# EctoControlAdapter.net
KiCad netlist of a schematic drawn in EasyEDA Pro
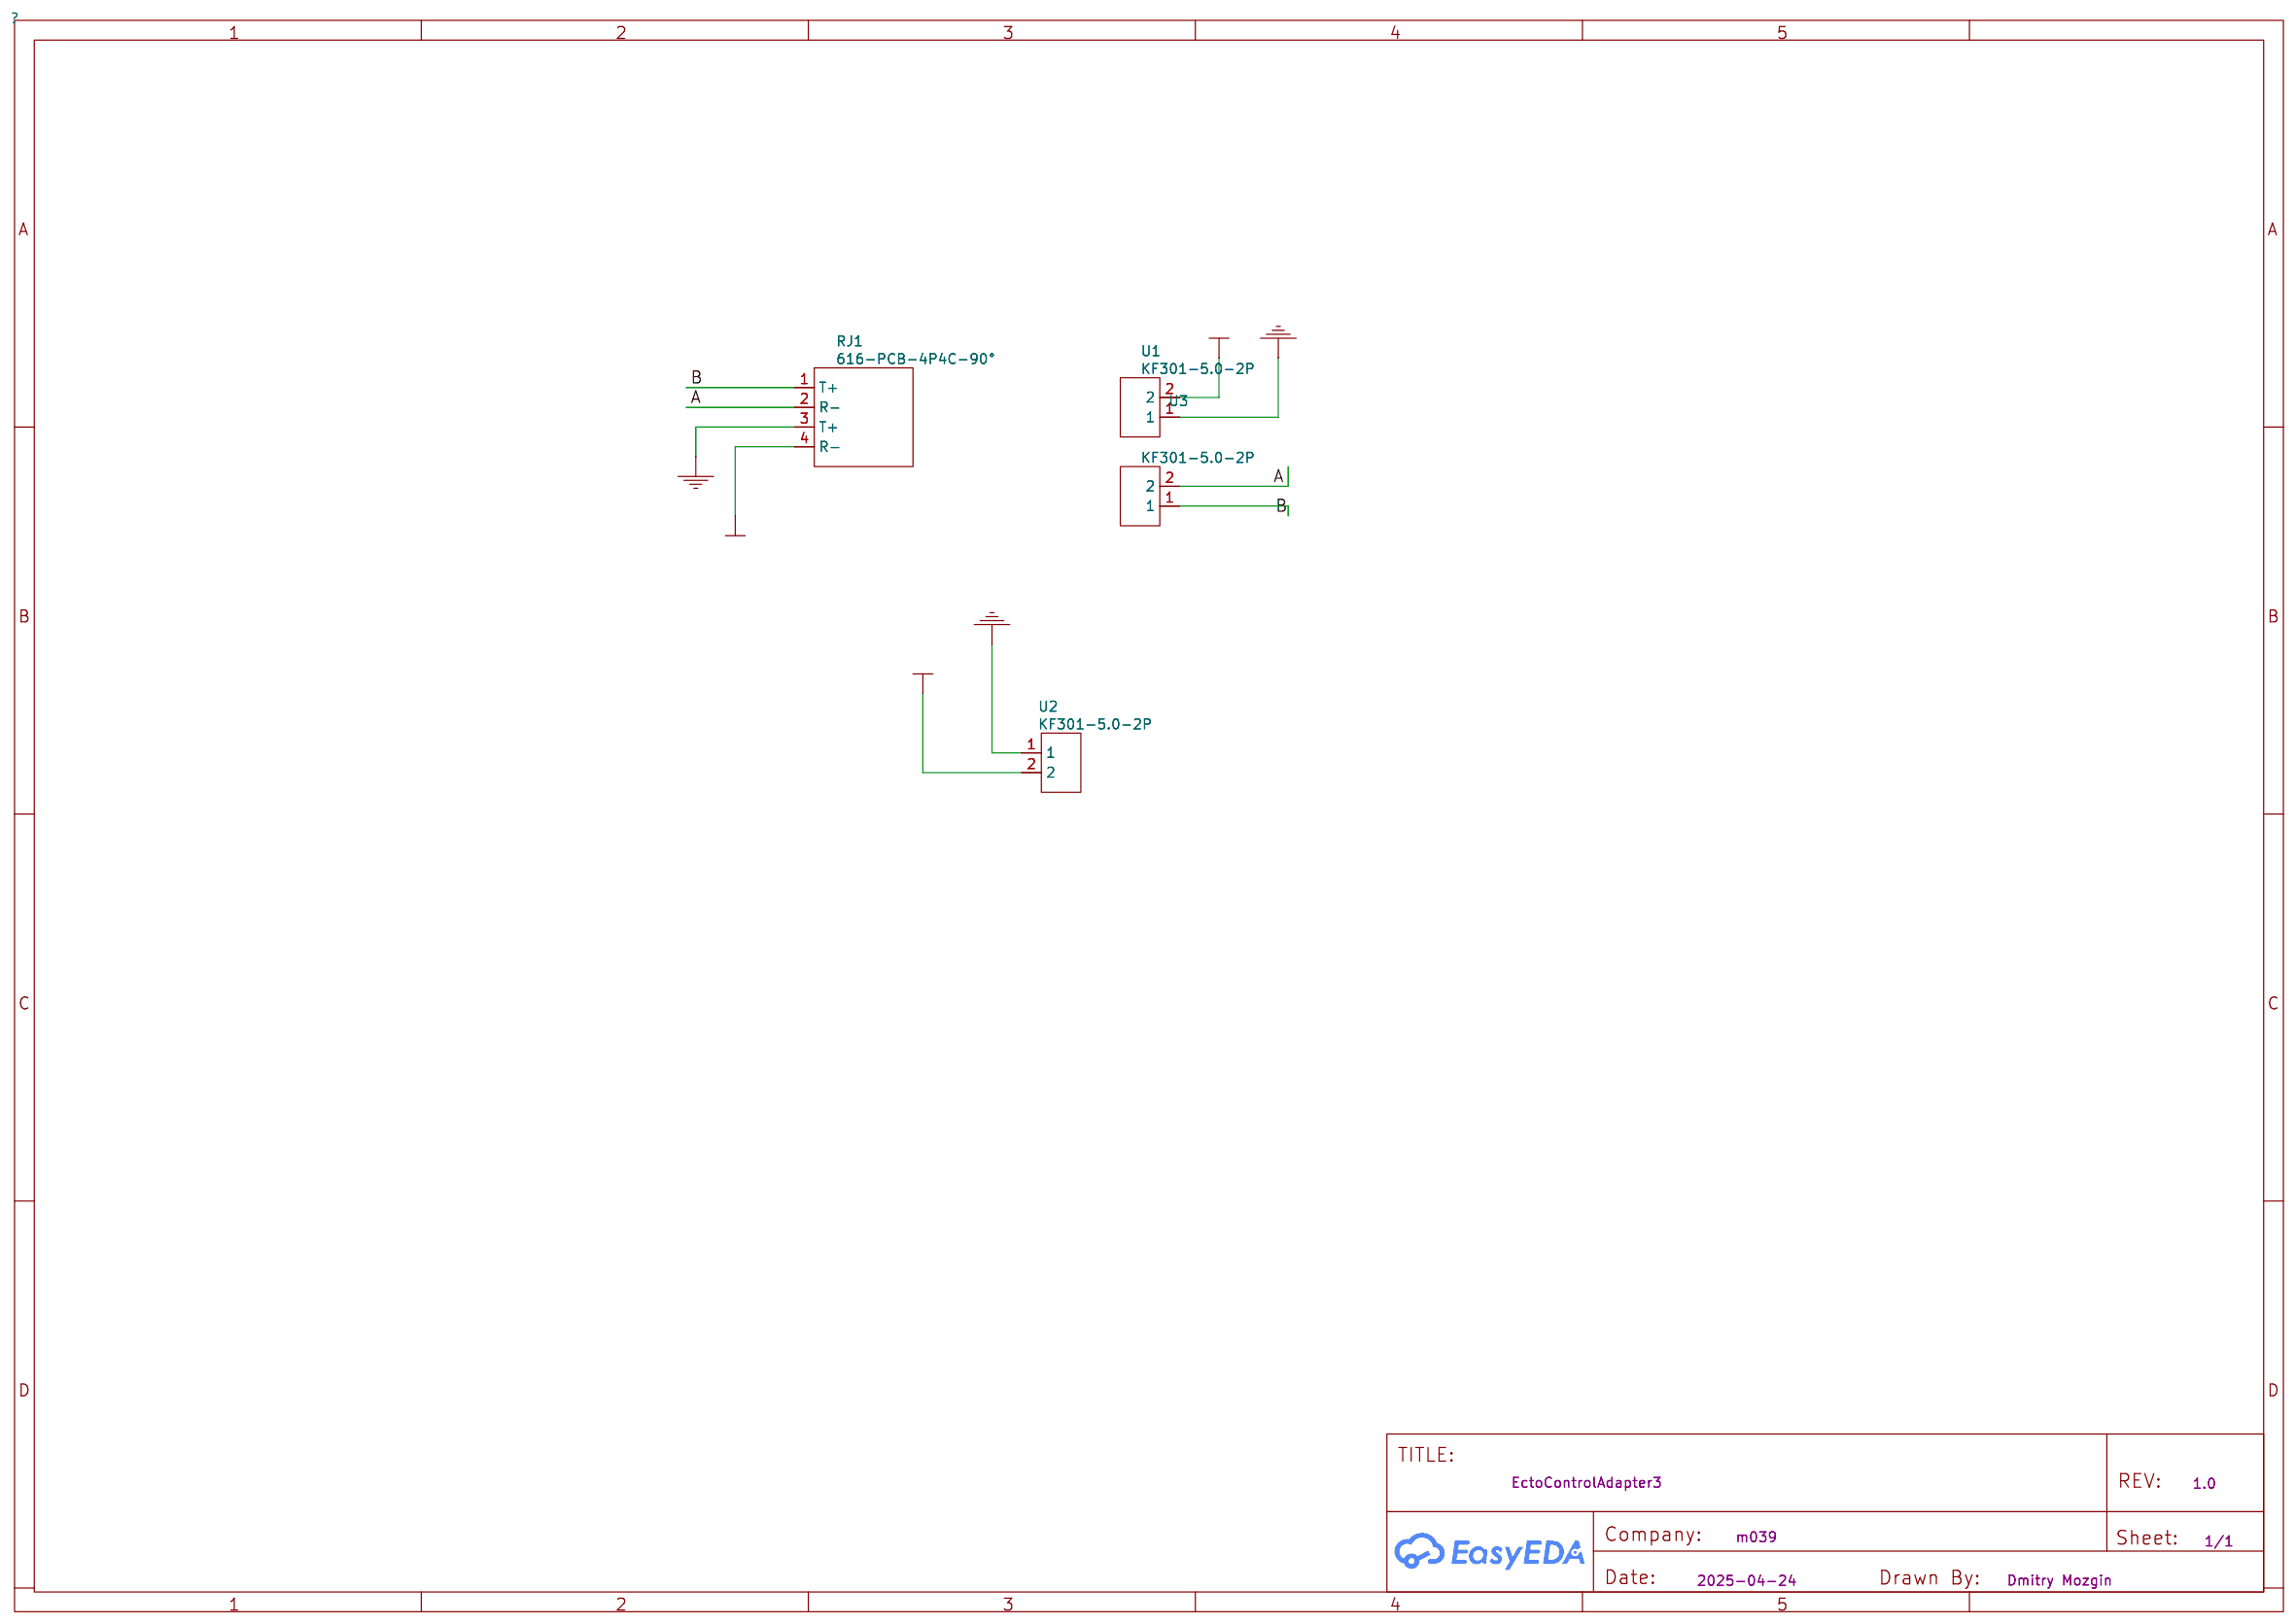
[diagram p0: schematic sheet]

(export (version "E")
  (design (tool "Eeschema 10.0.6"))
  (components
    (comp (ref "RJ1")
      (value "616-PCB-4P4C-90°")
      (footprint "easyedapro:RJ11-TH_616-PCB-4P4C-90")
      (fields (field (name "Manufacturer Part") "R-RJ11R04P-A802") (field (name "Manufacturer") "Ckmtw(灿科盟)"))
      (libsource (lib "easyedapro") (part "616-PCB-4P4C-90°"))
    )
    (comp (ref "U1")
      (value "KF301-5.0-2P")
      (footprint "easyedapro:CONN-TH_P5.00_KF301-5.0-2P")
      (fields (field (name "Manufacturer") "KEFA(科发)"))
      (libsource (lib "easyedapro") (part "KF301-5.0-2P"))
    )
    (comp (ref "U2")
      (value "KF301-5.0-2P")
      (footprint "easyedapro:CONN-TH_P5.00_KF301-5.0-2P")
      (fields (field (name "Manufacturer") "KEFA(科发)"))
      (libsource (lib "") (part "KF301-5.0-2P_1"))
    )
    (comp (ref "U3")
      (value "KF301-5.0-2P")
      (footprint "easyedapro:CONN-TH_P5.00_KF301-5.0-2P")
      (fields (field (name "Manufacturer") "KEFA(科发)"))
      (libsource (lib "easyedapro") (part "KF301-5.0-2P"))
    )
  )
  (nets
    (net (code "1") (name "/A") (class "Default")
      (node (ref "RJ1") (pin "2") (pinfunction "R-_2") (pintype "unspecified"))
      (node (ref "U3") (pin "2") (pinfunction "2_2") (pintype "unspecified"))
    )
    (net (code "2") (name "/B") (class "Default")
      (node (ref "RJ1") (pin "1") (pinfunction "T+_1") (pintype "unspecified"))
      (node (ref "U3") (pin "1") (pinfunction "1_1") (pintype "unspecified"))
    )
    (net (code "3") (name "GND") (class "Default")
      (node (ref "RJ1") (pin "3") (pinfunction "T+_3") (pintype "unspecified"))
      (node (ref "U1") (pin "1") (pinfunction "1_1") (pintype "unspecified"))
      (node (ref "U2") (pin "1") (pinfunction "1_1") (pintype "unspecified"))
    )
    (net (code "4") (name "VCC") (class "Default")
      (node (ref "RJ1") (pin "4") (pinfunction "R-_4") (pintype "unspecified"))
      (node (ref "U1") (pin "2") (pinfunction "2_2") (pintype "unspecified"))
      (node (ref "U2") (pin "2") (pinfunction "2_2") (pintype "unspecified"))
    )
  )
)
